# 13-Digital.net
KiCad netlist of a schematic drawn in Altium Designer
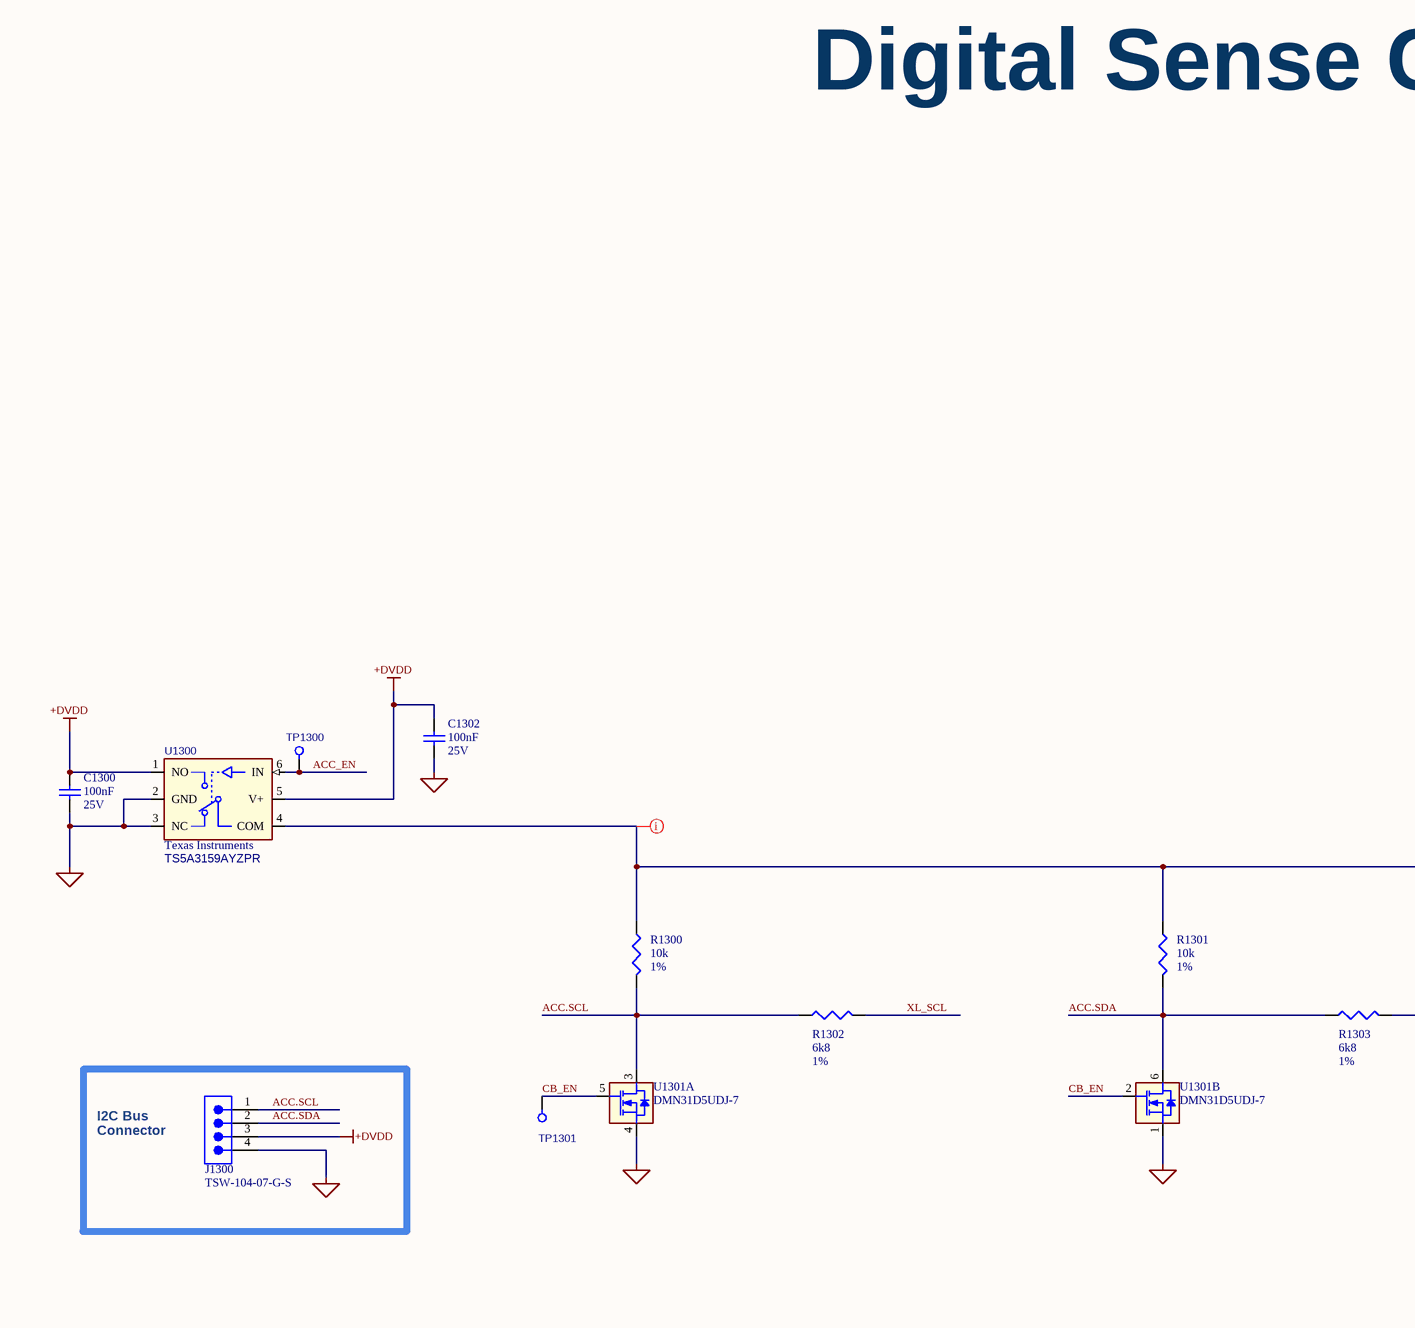
[diagram p0: 13-Digital.SchDoc, left]
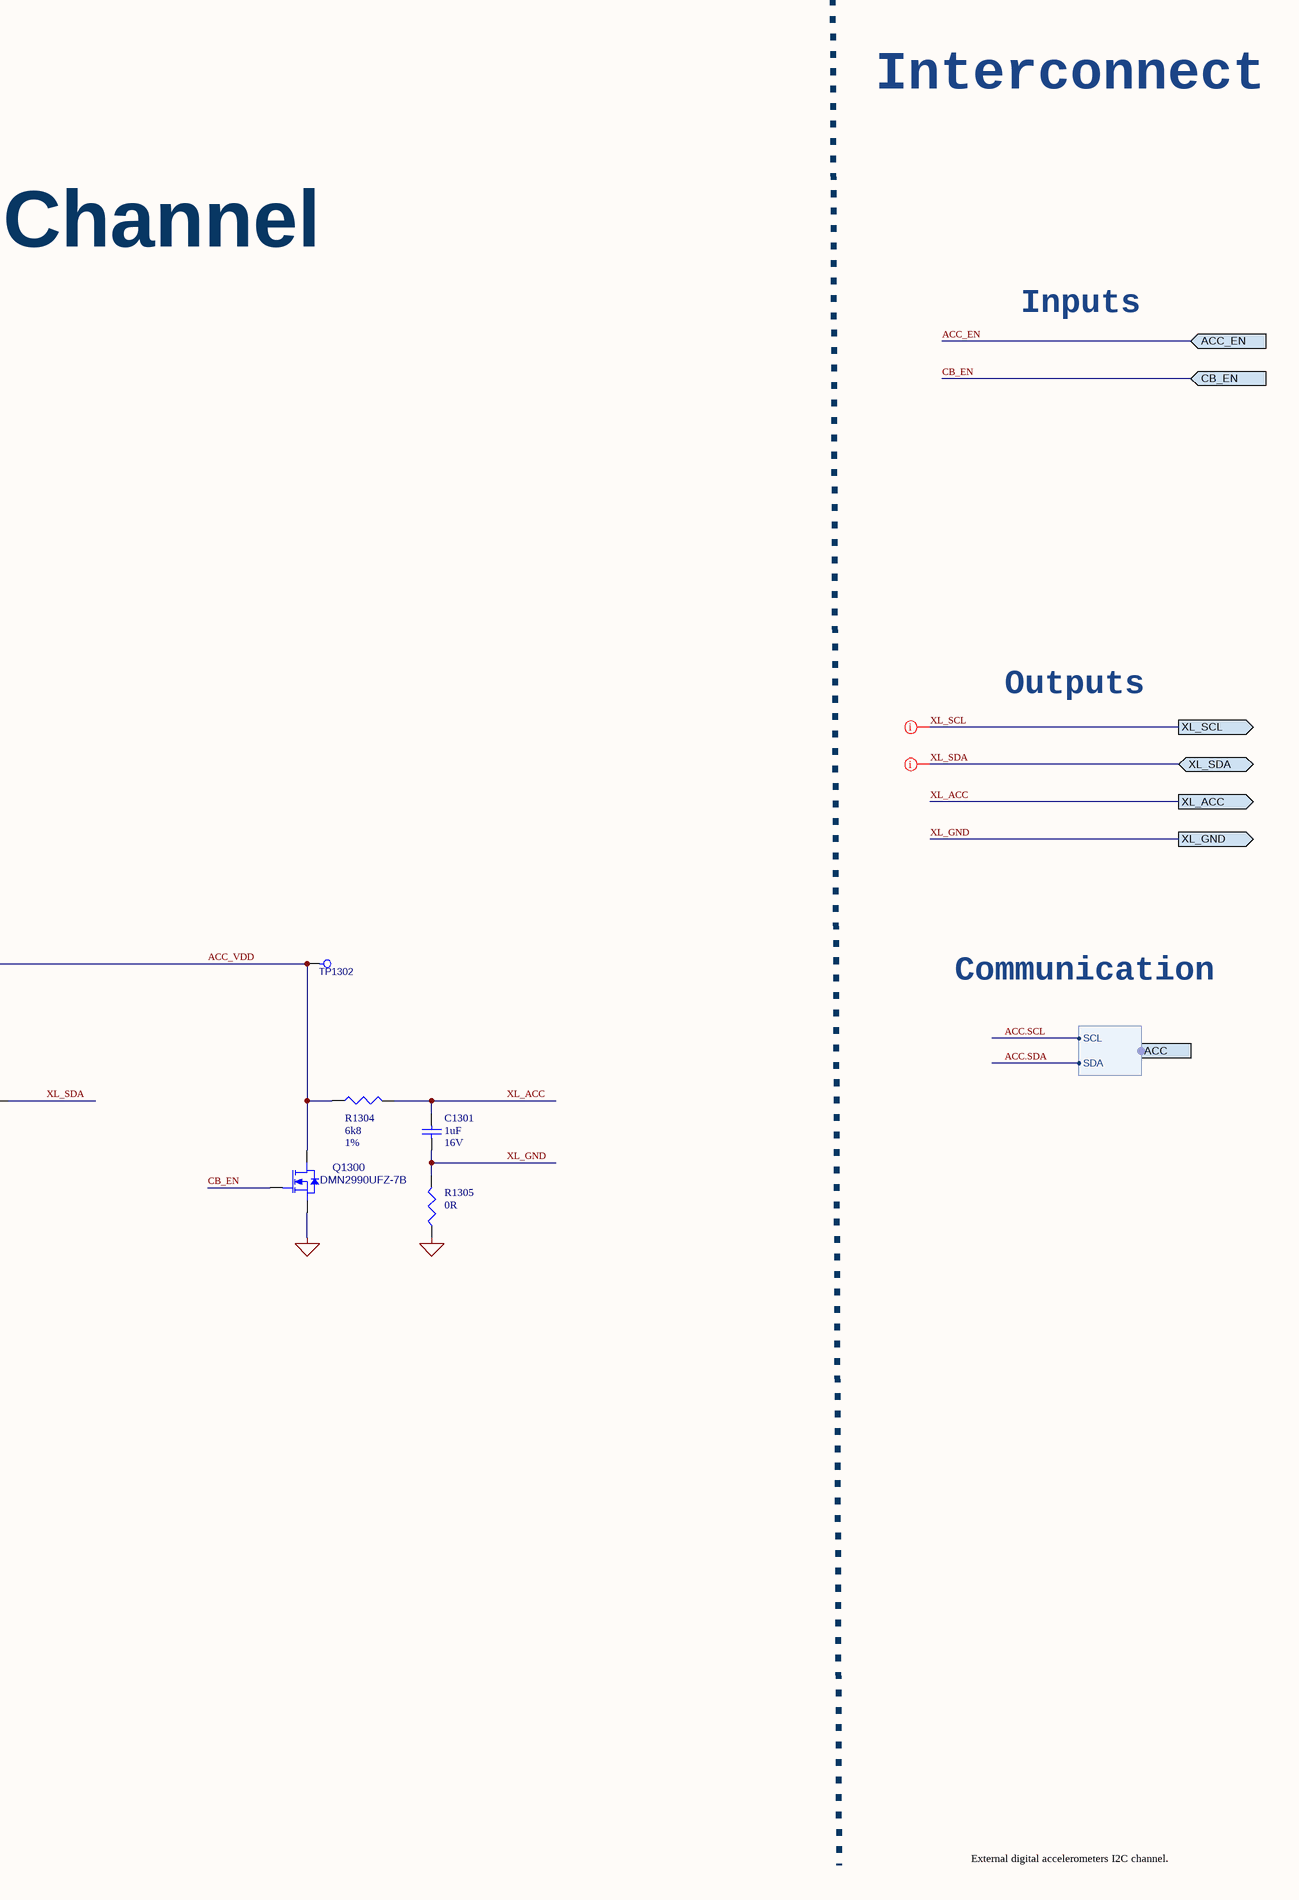
[diagram p1: 13-Digital.SchDoc, right]

(export (version "E")
  (design (tool "Eeschema 10.0.6"))
  (components
    (comp (ref "C1300")
      (value "100nF")
      (footprint "C0201_C")
      (fields
        (field (name "MANUFACTURER") "Murata")
        (field (name "MANUFACTURER PART NUMBER") "GRM033R61E104KE14J")
        (field (name "RATED DC VOLTAGE (URDC)") "25V")
      )
      (libsource (lib "MP-LIBRARY") (part "GRM033R61E104KE14J"))
    )
    (comp (ref "C1301")
      (value "1uF")
      (footprint "C0201_C")
      (fields
        (field (name "MANUFACTURER") "Murata")
        (field (name "MANUFACTURER PART NUMBER") "GRM033R61C105ME15D")
        (field (name "RATED DC VOLTAGE (URDC)") "16V")
      )
      (libsource (lib "MP-LIBRARY") (part "GRM033R61C105ME15D"))
    )
    (comp (ref "C1302")
      (value "100nF")
      (footprint "C0201_C")
      (fields
        (field (name "MANUFACTURER") "Murata")
        (field (name "MANUFACTURER PART NUMBER") "GRM033R61E104KE14J")
        (field (name "RATED DC VOLTAGE (URDC)") "25V")
      )
      (libsource (lib "MP-LIBRARY") (part "GRM033R61E104KE14J"))
    )
    (comp (ref "J1300")
      (value "TSW-104-07-G-S")
      (footprint "SMTC-TSW-104-07-X-S")
      (fields (field (name "MANUFACTURER") "Samtec") (field (name "PARTNUMBER") "TSW-106-07-G-S"))
      (libsource (lib "MP-LIBRARY") (part "TSW-104-07-G-S"))
    )
    (comp (ref "Q1300")
      (value "DMN2990UFZ-7B")
      (footprint "DIODESINC_X2-DFN0606-3")
      (description "MOSFET, N-Chan, 20V, 170mA, DFN0606")
      (fields (field (name "MANUFACTURER") "Diodes Inc"))
      (libsource (lib "MP-LIBRARY") (part "DMN2990UFZ-7B"))
    )
    (comp (ref "R1300")
      (value "10k")
      (footprint "R0201_C")
      (fields
        (field (name "TOLERANCE") "1%")
        (field (name "MANUFACTURER") "Vishay")
        (field (name "MANUFACTURER PART NUMBER") "CRCW020110K0FNED")
        (field (name "POWER") "50mW")
      )
      (libsource (lib "MP-LIBRARY") (part "CRCW020110K0FNED"))
    )
    (comp (ref "R1301")
      (value "10k")
      (footprint "R0201_C")
      (fields
        (field (name "TOLERANCE") "1%")
        (field (name "MANUFACTURER") "Vishay")
        (field (name "MANUFACTURER PART NUMBER") "CRCW020110K0FNED")
        (field (name "POWER") "50mW")
      )
      (libsource (lib "MP-LIBRARY") (part "CRCW020110K0FNED"))
    )
    (comp (ref "R1302")
      (value "6k8")
      (footprint "R0201_C")
      (fields
        (field (name "TOLERANCE") "1%")
        (field (name "MANUFACTURER") "Vishay")
        (field (name "MANUFACTURER PART NUMBER") "CRCW02016K80FNED")
        (field (name "POWER") "50mW")
      )
      (libsource (lib "MP-LIBRARY") (part "CRCW02016K80FNED"))
    )
    (comp (ref "R1303")
      (value "6k8")
      (footprint "R0201_C")
      (fields
        (field (name "TOLERANCE") "1%")
        (field (name "MANUFACTURER") "Vishay")
        (field (name "MANUFACTURER PART NUMBER") "CRCW02016K80FNED")
        (field (name "POWER") "50mW")
      )
      (libsource (lib "MP-LIBRARY") (part "CRCW02016K80FNED"))
    )
    (comp (ref "R1304")
      (value "6k8")
      (footprint "R0201_C")
      (fields
        (field (name "TOLERANCE") "1%")
        (field (name "MANUFACTURER") "Vishay")
        (field (name "MANUFACTURER PART NUMBER") "CRCW02016K80FNED")
        (field (name "POWER") "50mW")
      )
      (libsource (lib "MP-LIBRARY") (part "CRCW02016K80FNED"))
    )
    (comp (ref "R1305")
      (value "0R")
      (footprint "R0201_C")
      (description "Fixed Resistor, Metal Glaze/thick Film, 0.05W, 0ohm, Surface Mount, 0201")
      (fields
        (field (name "MANUFACTURER") "Vishay")
        (field (name "MANUFACTURER PART NUMBER") "CRCW02010000Z0ED")
      )
      (libsource (lib "MP-LIBRARY") (part "CRCW02010000Z0ED"))
    )
    (comp (ref "TP1300")
      (value "Test Point")
      (footprint "testpad_0.9mm")
      (description "Test pad, 0.90mm circular pad")
      (libsource (lib "MP-LIBRARY") (part "Test Point"))
    )
    (comp (ref "TP1301")
      (value "Test Point")
      (footprint "testpad_0.9mm")
      (description "Test pad, 0.90mm circular pad")
      (libsource (lib "MP-LIBRARY") (part "Test Point"))
    )
    (comp (ref "TP1302")
      (value "Test Point")
      (footprint "testpad_0.9mm")
      (description "Test pad, 0.90mm circular pad")
      (libsource (lib "MP-LIBRARY") (part "Test Point"))
    )
    (comp (ref "U1300")
      (value "TS5A3159AYZPR")
      (footprint "TI_YZP6")
      (description "Analog Switch, SPDT, 2:1, DSBGA6")
      (fields (field (name "MANUFACTURER") "Texas Instruments"))
      (libsource (lib "MP-LIBRARY") (part "TS5A3159AYZPR"))
    )
    (comp (ref "U1301")
      (value "DMN31D5UDJ-7")
      (footprint "DIODESINC_SOT-963-6")
      (description "MOSFET 2N-CH 30V 0.22A SOT963")
      (fields (field (name "MANUFACTURER") "Diodes inc."))
      (libsource (lib "MP-LIBRARY") (part "DMN31D5UDJ-7"))
    )
  )
  (nets
    (net (code "2") (name "+DVDD") (class "Default")
      (node (ref "C1300") (pin "2") (pinfunction "2_2") (pintype "passive"))
      (node (ref "C1302") (pin "2") (pinfunction "2_2") (pintype "passive"))
      (node (ref "J1300") (pin "3") (pinfunction "3_3") (pintype "passive"))
      (node (ref "U1300") (pin "1") (pinfunction "NO_1") (pintype "passive"))
      (node (ref "U1300") (pin "5") (pinfunction "V+_5") (pintype "power_in"))
    )
    (net (code "3") (name "/ACC.SCL") (class "Default")
      (node (ref "J1300") (pin "1") (pinfunction "1_1") (pintype "passive"))
      (node (ref "R1300") (pin "2") (pinfunction "2_2") (pintype "passive"))
      (node (ref "R1302") (pin "1") (pinfunction "1_1") (pintype "passive"))
      (node (ref "U1301") (pin "3") (pinfunction "3_3") (pintype "passive"))
    )
    (net (code "4") (name "/ACC.SDA") (class "Default")
      (node (ref "J1300") (pin "2") (pinfunction "2_2") (pintype "passive"))
      (node (ref "R1301") (pin "2") (pinfunction "2_2") (pintype "passive"))
      (node (ref "R1303") (pin "1") (pinfunction "1_1") (pintype "passive"))
      (node (ref "U1301") (pin "6") (pinfunction "6_6") (pintype "passive"))
    )
    (net (code "5") (name "/ACC_EN") (class "Default")
      (node (ref "TP1300") (pin "1") (pinfunction "1_1") (pintype "passive"))
      (node (ref "U1300") (pin "6") (pinfunction "IN_6") (pintype "input"))
    )
    (net (code "6") (name "/ACC_VDD") (class "Default")
      (node (ref "Q1300") (pin "3") (pinfunction "D_3") (pintype "passive"))
      (node (ref "R1300") (pin "1") (pinfunction "1_1") (pintype "passive"))
      (node (ref "R1301") (pin "1") (pinfunction "1_1") (pintype "passive"))
      (node (ref "R1304") (pin "1") (pinfunction "1_1") (pintype "passive"))
      (node (ref "TP1302") (pin "1") (pinfunction "1_1") (pintype "passive"))
      (node (ref "U1300") (pin "4") (pinfunction "COM_4") (pintype "passive"))
    )
    (net (code "7") (name "/CB_EN") (class "Default")
      (node (ref "Q1300") (pin "1") (pinfunction "G_1") (pintype "passive"))
      (node (ref "TP1301") (pin "1") (pinfunction "1_1") (pintype "passive"))
      (node (ref "U1301") (pin "2") (pinfunction "2_2") (pintype "passive"))
      (node (ref "U1301") (pin "5") (pinfunction "5_5") (pintype "passive"))
    )
    (net (code "8") (name "/XL_ACC") (class "Default")
      (node (ref "C1301") (pin "2") (pinfunction "2_2") (pintype "passive"))
      (node (ref "R1304") (pin "2") (pinfunction "2_2") (pintype "passive"))
    )
    (net (code "9") (name "/XL_GND") (class "Default")
      (node (ref "C1301") (pin "1") (pinfunction "1_1") (pintype "passive"))
      (node (ref "R1305") (pin "2") (pinfunction "2_2") (pintype "passive"))
    )
    (net (code "10") (name "/XL_SCL") (class "Default")
      (node (ref "R1302") (pin "2") (pinfunction "2_2") (pintype "passive"))
    )
    (net (code "11") (name "/XL_SDA") (class "Default")
      (node (ref "R1303") (pin "2") (pinfunction "2_2") (pintype "passive"))
    )
    (net (code "13") (name "GND") (class "Default")
      (node (ref "C1300") (pin "1") (pinfunction "1_1") (pintype "passive"))
      (node (ref "C1302") (pin "1") (pinfunction "1_1") (pintype "passive"))
      (node (ref "J1300") (pin "4") (pinfunction "4_4") (pintype "passive"))
      (node (ref "Q1300") (pin "2") (pinfunction "S_2") (pintype "passive"))
      (node (ref "R1305") (pin "1") (pinfunction "1_1") (pintype "passive"))
      (node (ref "U1300") (pin "2") (pinfunction "GND_2") (pintype "power_in"))
      (node (ref "U1300") (pin "3") (pinfunction "NC_3") (pintype "passive"))
      (node (ref "U1301") (pin "1") (pinfunction "1_1") (pintype "passive"))
      (node (ref "U1301") (pin "4") (pinfunction "4_4") (pintype "passive"))
    )
  )
)
